# cblock-vrs.net
KiCad netlist of a schematic drawn in EAGLE
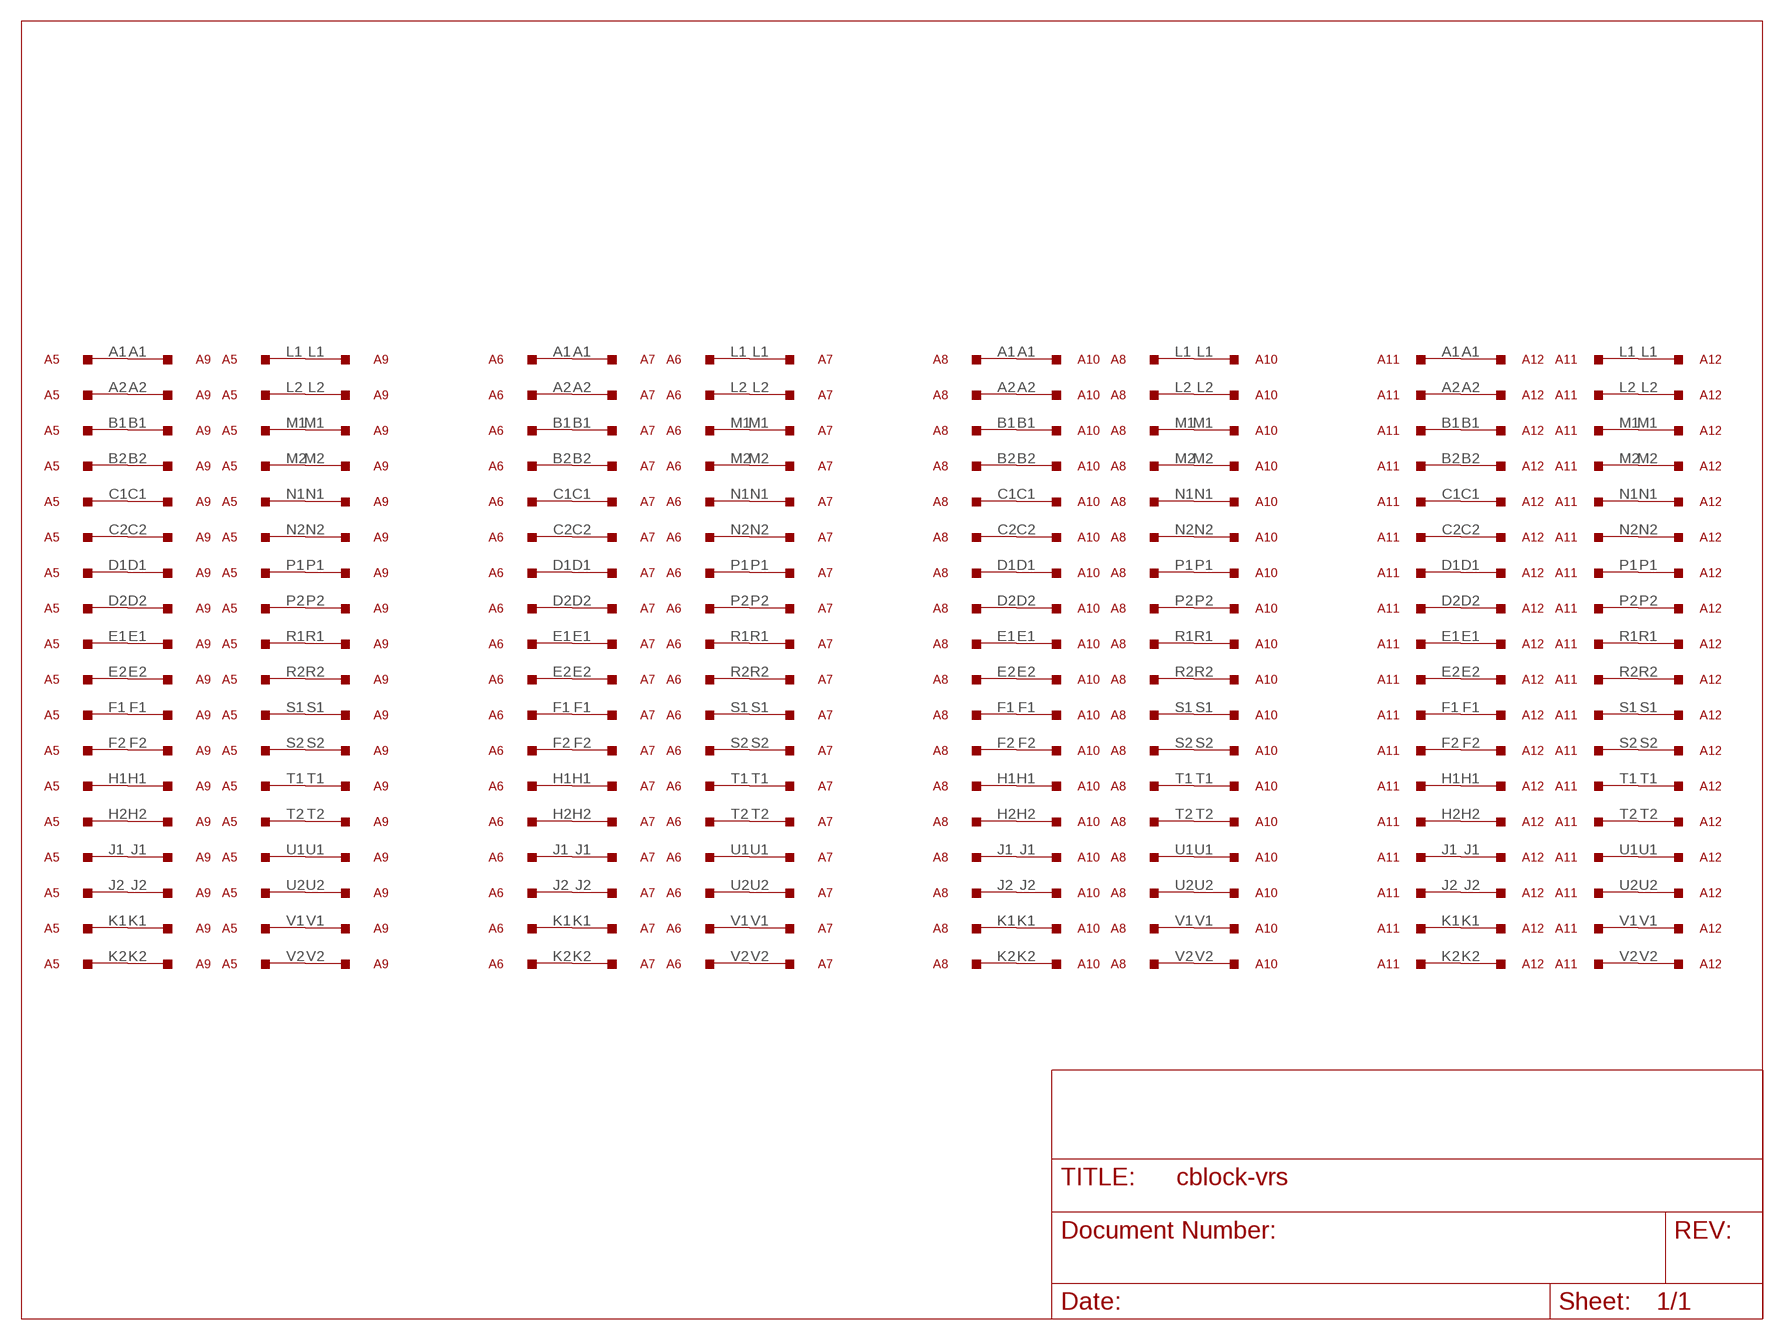
[diagram p0: schematic, sheet 1]

(export (version "E")
  (design (tool "Eeschema 10.0.6"))
  (components
    (comp (ref "A5")
      (value "M916")
      (footprint "eagle-import:H807")
      (libsource (lib "eagle-import") (part "M916"))
    )
    (comp (ref "A6")
      (value "M916")
      (footprint "eagle-import:H807")
      (libsource (lib "eagle-import") (part "M916"))
    )
    (comp (ref "A7")
      (value "M916")
      (footprint "eagle-import:H807")
      (libsource (lib "eagle-import") (part "M916"))
    )
    (comp (ref "A8")
      (value "M916")
      (footprint "eagle-import:H807")
      (libsource (lib "eagle-import") (part "M916"))
    )
    (comp (ref "A9")
      (value "M916")
      (footprint "eagle-import:H807")
      (libsource (lib "eagle-import") (part "M916"))
    )
    (comp (ref "A10")
      (value "M916")
      (footprint "eagle-import:H807")
      (libsource (lib "eagle-import") (part "M916"))
    )
    (comp (ref "A11")
      (value "M916")
      (footprint "eagle-import:H807")
      (libsource (lib "eagle-import") (part "M916"))
    )
    (comp (ref "A12")
      (value "M916")
      (footprint "eagle-import:H807")
      (libsource (lib "eagle-import") (part "M916"))
    )
  )
  (nets
    (net (code "1") (name "Net-(A5A-P$2)") (class "Default")
      (node (ref "A5") (pin "A1") (pinfunction "P$2_A1") (pintype "bidirectional"))
      (node (ref "A9") (pin "A1") (pinfunction "P$2_A1") (pintype "bidirectional"))
    )
    (net (code "2") (name "Net-(A5AA-P$2)") (class "Default")
      (node (ref "A5") (pin "R1") (pinfunction "P$2_R1") (pintype "bidirectional"))
      (node (ref "A9") (pin "R1") (pinfunction "P$2_R1") (pintype "bidirectional"))
    )
    (net (code "3") (name "Net-(A5AB-P$2)") (class "Default")
      (node (ref "A5") (pin "R2") (pinfunction "P$2_R2") (pintype "bidirectional"))
      (node (ref "A9") (pin "R2") (pinfunction "P$2_R2") (pintype "bidirectional"))
    )
    (net (code "4") (name "Net-(A5AC-P$2)") (class "Default")
      (node (ref "A5") (pin "S1") (pinfunction "P$2_S1") (pintype "bidirectional"))
      (node (ref "A9") (pin "S1") (pinfunction "P$2_S1") (pintype "bidirectional"))
    )
    (net (code "5") (name "Net-(A5AD-P$2)") (class "Default")
      (node (ref "A5") (pin "S2") (pinfunction "P$2_S2") (pintype "bidirectional"))
      (node (ref "A9") (pin "S2") (pinfunction "P$2_S2") (pintype "bidirectional"))
    )
    (net (code "6") (name "Net-(A5AE-P$2)") (class "Default")
      (node (ref "A5") (pin "T1") (pinfunction "P$2_T1") (pintype "bidirectional"))
      (node (ref "A9") (pin "T1") (pinfunction "P$2_T1") (pintype "bidirectional"))
    )
    (net (code "7") (name "Net-(A5AF-P$2)") (class "Default")
      (node (ref "A5") (pin "T2") (pinfunction "P$2_T2") (pintype "bidirectional"))
      (node (ref "A9") (pin "T2") (pinfunction "P$2_T2") (pintype "bidirectional"))
    )
    (net (code "8") (name "Net-(A5AG-P$2)") (class "Default")
      (node (ref "A5") (pin "U1") (pinfunction "P$2_U1") (pintype "bidirectional"))
      (node (ref "A9") (pin "U1") (pinfunction "P$2_U1") (pintype "bidirectional"))
    )
    (net (code "9") (name "Net-(A5AH-P$2)") (class "Default")
      (node (ref "A5") (pin "U2") (pinfunction "P$2_U2") (pintype "bidirectional"))
      (node (ref "A9") (pin "U2") (pinfunction "P$2_U2") (pintype "bidirectional"))
    )
    (net (code "10") (name "Net-(A5AI-P$2)") (class "Default")
      (node (ref "A5") (pin "V1") (pinfunction "P$2_V1") (pintype "bidirectional"))
      (node (ref "A9") (pin "V1") (pinfunction "P$2_V1") (pintype "bidirectional"))
    )
    (net (code "11") (name "Net-(A5AJ-P$2)") (class "Default")
      (node (ref "A5") (pin "V2") (pinfunction "P$2_V2") (pintype "bidirectional"))
      (node (ref "A9") (pin "V2") (pinfunction "P$2_V2") (pintype "bidirectional"))
    )
    (net (code "12") (name "Net-(A5B-P$2)") (class "Default")
      (node (ref "A5") (pin "A2") (pinfunction "P$2_A2") (pintype "bidirectional"))
      (node (ref "A9") (pin "A2") (pinfunction "P$2_A2") (pintype "bidirectional"))
    )
    (net (code "13") (name "Net-(A5C-P$2)") (class "Default")
      (node (ref "A5") (pin "B1") (pinfunction "P$2_B1") (pintype "bidirectional"))
      (node (ref "A9") (pin "B1") (pinfunction "P$2_B1") (pintype "bidirectional"))
    )
    (net (code "14") (name "Net-(A5D-P$2)") (class "Default")
      (node (ref "A5") (pin "B2") (pinfunction "P$2_B2") (pintype "bidirectional"))
      (node (ref "A9") (pin "B2") (pinfunction "P$2_B2") (pintype "bidirectional"))
    )
    (net (code "15") (name "Net-(A5E-P$2)") (class "Default")
      (node (ref "A5") (pin "C1") (pinfunction "P$2_C1") (pintype "bidirectional"))
      (node (ref "A9") (pin "C1") (pinfunction "P$2_C1") (pintype "bidirectional"))
    )
    (net (code "16") (name "Net-(A5F-P$2)") (class "Default")
      (node (ref "A5") (pin "C2") (pinfunction "P$2_C2") (pintype "bidirectional"))
      (node (ref "A9") (pin "C2") (pinfunction "P$2_C2") (pintype "bidirectional"))
    )
    (net (code "17") (name "Net-(A5G-P$2)") (class "Default")
      (node (ref "A5") (pin "D1") (pinfunction "P$2_D1") (pintype "bidirectional"))
      (node (ref "A9") (pin "D1") (pinfunction "P$2_D1") (pintype "bidirectional"))
    )
    (net (code "18") (name "Net-(A5H-P$2)") (class "Default")
      (node (ref "A5") (pin "D2") (pinfunction "P$2_D2") (pintype "bidirectional"))
      (node (ref "A9") (pin "D2") (pinfunction "P$2_D2") (pintype "bidirectional"))
    )
    (net (code "19") (name "Net-(A5I-P$2)") (class "Default")
      (node (ref "A5") (pin "E1") (pinfunction "P$2_E1") (pintype "bidirectional"))
      (node (ref "A9") (pin "E1") (pinfunction "P$2_E1") (pintype "bidirectional"))
    )
    (net (code "20") (name "Net-(A5J-P$2)") (class "Default")
      (node (ref "A5") (pin "E2") (pinfunction "P$2_E2") (pintype "bidirectional"))
      (node (ref "A9") (pin "E2") (pinfunction "P$2_E2") (pintype "bidirectional"))
    )
    (net (code "21") (name "Net-(A5K-P$2)") (class "Default")
      (node (ref "A5") (pin "F1") (pinfunction "P$2_F1") (pintype "bidirectional"))
      (node (ref "A9") (pin "F1") (pinfunction "P$2_F1") (pintype "bidirectional"))
    )
    (net (code "22") (name "Net-(A5L-P$2)") (class "Default")
      (node (ref "A5") (pin "F2") (pinfunction "P$2_F2") (pintype "bidirectional"))
      (node (ref "A9") (pin "F2") (pinfunction "P$2_F2") (pintype "bidirectional"))
    )
    (net (code "23") (name "Net-(A5M-P$2)") (class "Default")
      (node (ref "A5") (pin "H1") (pinfunction "P$2_H1") (pintype "bidirectional"))
      (node (ref "A9") (pin "H1") (pinfunction "P$2_H1") (pintype "bidirectional"))
    )
    (net (code "24") (name "Net-(A5N-P$2)") (class "Default")
      (node (ref "A5") (pin "H2") (pinfunction "P$2_H2") (pintype "bidirectional"))
      (node (ref "A9") (pin "H2") (pinfunction "P$2_H2") (pintype "bidirectional"))
    )
    (net (code "25") (name "Net-(A5O-P$2)") (class "Default")
      (node (ref "A5") (pin "J1") (pinfunction "P$2_J1") (pintype "bidirectional"))
      (node (ref "A9") (pin "J1") (pinfunction "P$2_J1") (pintype "bidirectional"))
    )
    (net (code "26") (name "Net-(A5P-P$2)") (class "Default")
      (node (ref "A5") (pin "J2") (pinfunction "P$2_J2") (pintype "bidirectional"))
      (node (ref "A9") (pin "J2") (pinfunction "P$2_J2") (pintype "bidirectional"))
    )
    (net (code "27") (name "Net-(A5Q-P$2)") (class "Default")
      (node (ref "A5") (pin "K1") (pinfunction "P$2_K1") (pintype "bidirectional"))
      (node (ref "A9") (pin "K1") (pinfunction "P$2_K1") (pintype "bidirectional"))
    )
    (net (code "28") (name "Net-(A5R-P$2)") (class "Default")
      (node (ref "A5") (pin "K2") (pinfunction "P$2_K2") (pintype "bidirectional"))
      (node (ref "A9") (pin "K2") (pinfunction "P$2_K2") (pintype "bidirectional"))
    )
    (net (code "29") (name "Net-(A5S-P$2)") (class "Default")
      (node (ref "A5") (pin "L1") (pinfunction "P$2_L1") (pintype "bidirectional"))
      (node (ref "A9") (pin "L1") (pinfunction "P$2_L1") (pintype "bidirectional"))
    )
    (net (code "30") (name "Net-(A5T-P$2)") (class "Default")
      (node (ref "A5") (pin "L2") (pinfunction "P$2_L2") (pintype "bidirectional"))
      (node (ref "A9") (pin "L2") (pinfunction "P$2_L2") (pintype "bidirectional"))
    )
    (net (code "31") (name "Net-(A5U-P$2)") (class "Default")
      (node (ref "A5") (pin "M1") (pinfunction "P$2_M1") (pintype "bidirectional"))
      (node (ref "A9") (pin "M1") (pinfunction "P$2_M1") (pintype "bidirectional"))
    )
    (net (code "32") (name "Net-(A5V-P$2)") (class "Default")
      (node (ref "A5") (pin "M2") (pinfunction "P$2_M2") (pintype "bidirectional"))
      (node (ref "A9") (pin "M2") (pinfunction "P$2_M2") (pintype "bidirectional"))
    )
    (net (code "33") (name "Net-(A5W-P$2)") (class "Default")
      (node (ref "A5") (pin "N1") (pinfunction "P$2_N1") (pintype "bidirectional"))
      (node (ref "A9") (pin "N1") (pinfunction "P$2_N1") (pintype "bidirectional"))
    )
    (net (code "34") (name "Net-(A5X-P$2)") (class "Default")
      (node (ref "A5") (pin "N2") (pinfunction "P$2_N2") (pintype "bidirectional"))
      (node (ref "A9") (pin "N2") (pinfunction "P$2_N2") (pintype "bidirectional"))
    )
    (net (code "35") (name "Net-(A5Y-P$2)") (class "Default")
      (node (ref "A5") (pin "P1") (pinfunction "P$2_P1") (pintype "bidirectional"))
      (node (ref "A9") (pin "P1") (pinfunction "P$2_P1") (pintype "bidirectional"))
    )
    (net (code "36") (name "Net-(A5Z-P$2)") (class "Default")
      (node (ref "A5") (pin "P2") (pinfunction "P$2_P2") (pintype "bidirectional"))
      (node (ref "A9") (pin "P2") (pinfunction "P$2_P2") (pintype "bidirectional"))
    )
    (net (code "37") (name "Net-(A6A-P$2)") (class "Default")
      (node (ref "A6") (pin "A1") (pinfunction "P$2_A1") (pintype "bidirectional"))
      (node (ref "A7") (pin "A1") (pinfunction "P$2_A1") (pintype "bidirectional"))
    )
    (net (code "38") (name "Net-(A6AA-P$2)") (class "Default")
      (node (ref "A6") (pin "R1") (pinfunction "P$2_R1") (pintype "bidirectional"))
      (node (ref "A7") (pin "R1") (pinfunction "P$2_R1") (pintype "bidirectional"))
    )
    (net (code "39") (name "Net-(A6AB-P$2)") (class "Default")
      (node (ref "A6") (pin "R2") (pinfunction "P$2_R2") (pintype "bidirectional"))
      (node (ref "A7") (pin "R2") (pinfunction "P$2_R2") (pintype "bidirectional"))
    )
    (net (code "40") (name "Net-(A6AC-P$2)") (class "Default")
      (node (ref "A6") (pin "S1") (pinfunction "P$2_S1") (pintype "bidirectional"))
      (node (ref "A7") (pin "S1") (pinfunction "P$2_S1") (pintype "bidirectional"))
    )
    (net (code "41") (name "Net-(A6AD-P$2)") (class "Default")
      (node (ref "A6") (pin "S2") (pinfunction "P$2_S2") (pintype "bidirectional"))
      (node (ref "A7") (pin "S2") (pinfunction "P$2_S2") (pintype "bidirectional"))
    )
    (net (code "42") (name "Net-(A6AE-P$2)") (class "Default")
      (node (ref "A6") (pin "T1") (pinfunction "P$2_T1") (pintype "bidirectional"))
      (node (ref "A7") (pin "T1") (pinfunction "P$2_T1") (pintype "bidirectional"))
    )
    (net (code "43") (name "Net-(A6AF-P$2)") (class "Default")
      (node (ref "A6") (pin "T2") (pinfunction "P$2_T2") (pintype "bidirectional"))
      (node (ref "A7") (pin "T2") (pinfunction "P$2_T2") (pintype "bidirectional"))
    )
    (net (code "44") (name "Net-(A6AG-P$2)") (class "Default")
      (node (ref "A6") (pin "U1") (pinfunction "P$2_U1") (pintype "bidirectional"))
      (node (ref "A7") (pin "U1") (pinfunction "P$2_U1") (pintype "bidirectional"))
    )
    (net (code "45") (name "Net-(A6AH-P$2)") (class "Default")
      (node (ref "A6") (pin "U2") (pinfunction "P$2_U2") (pintype "bidirectional"))
      (node (ref "A7") (pin "U2") (pinfunction "P$2_U2") (pintype "bidirectional"))
    )
    (net (code "46") (name "Net-(A6AI-P$2)") (class "Default")
      (node (ref "A6") (pin "V1") (pinfunction "P$2_V1") (pintype "bidirectional"))
      (node (ref "A7") (pin "V1") (pinfunction "P$2_V1") (pintype "bidirectional"))
    )
    (net (code "47") (name "Net-(A6AJ-P$2)") (class "Default")
      (node (ref "A6") (pin "V2") (pinfunction "P$2_V2") (pintype "bidirectional"))
      (node (ref "A7") (pin "V2") (pinfunction "P$2_V2") (pintype "bidirectional"))
    )
    (net (code "48") (name "Net-(A6B-P$2)") (class "Default")
      (node (ref "A6") (pin "A2") (pinfunction "P$2_A2") (pintype "bidirectional"))
      (node (ref "A7") (pin "A2") (pinfunction "P$2_A2") (pintype "bidirectional"))
    )
    (net (code "49") (name "Net-(A6C-P$2)") (class "Default")
      (node (ref "A6") (pin "B1") (pinfunction "P$2_B1") (pintype "bidirectional"))
      (node (ref "A7") (pin "B1") (pinfunction "P$2_B1") (pintype "bidirectional"))
    )
    (net (code "50") (name "Net-(A6D-P$2)") (class "Default")
      (node (ref "A6") (pin "B2") (pinfunction "P$2_B2") (pintype "bidirectional"))
      (node (ref "A7") (pin "B2") (pinfunction "P$2_B2") (pintype "bidirectional"))
    )
    (net (code "51") (name "Net-(A6E-P$2)") (class "Default")
      (node (ref "A6") (pin "C1") (pinfunction "P$2_C1") (pintype "bidirectional"))
      (node (ref "A7") (pin "C1") (pinfunction "P$2_C1") (pintype "bidirectional"))
    )
    (net (code "52") (name "Net-(A6F-P$2)") (class "Default")
      (node (ref "A6") (pin "C2") (pinfunction "P$2_C2") (pintype "bidirectional"))
      (node (ref "A7") (pin "C2") (pinfunction "P$2_C2") (pintype "bidirectional"))
    )
    (net (code "53") (name "Net-(A6G-P$2)") (class "Default")
      (node (ref "A6") (pin "D1") (pinfunction "P$2_D1") (pintype "bidirectional"))
      (node (ref "A7") (pin "D1") (pinfunction "P$2_D1") (pintype "bidirectional"))
    )
    (net (code "54") (name "Net-(A6H-P$2)") (class "Default")
      (node (ref "A6") (pin "D2") (pinfunction "P$2_D2") (pintype "bidirectional"))
      (node (ref "A7") (pin "D2") (pinfunction "P$2_D2") (pintype "bidirectional"))
    )
    (net (code "55") (name "Net-(A6I-P$2)") (class "Default")
      (node (ref "A6") (pin "E1") (pinfunction "P$2_E1") (pintype "bidirectional"))
      (node (ref "A7") (pin "E1") (pinfunction "P$2_E1") (pintype "bidirectional"))
    )
    (net (code "56") (name "Net-(A6J-P$2)") (class "Default")
      (node (ref "A6") (pin "E2") (pinfunction "P$2_E2") (pintype "bidirectional"))
      (node (ref "A7") (pin "E2") (pinfunction "P$2_E2") (pintype "bidirectional"))
    )
    (net (code "57") (name "Net-(A6K-P$2)") (class "Default")
      (node (ref "A6") (pin "F1") (pinfunction "P$2_F1") (pintype "bidirectional"))
      (node (ref "A7") (pin "F1") (pinfunction "P$2_F1") (pintype "bidirectional"))
    )
    (net (code "58") (name "Net-(A6L-P$2)") (class "Default")
      (node (ref "A6") (pin "F2") (pinfunction "P$2_F2") (pintype "bidirectional"))
      (node (ref "A7") (pin "F2") (pinfunction "P$2_F2") (pintype "bidirectional"))
    )
    (net (code "59") (name "Net-(A6M-P$2)") (class "Default")
      (node (ref "A6") (pin "H1") (pinfunction "P$2_H1") (pintype "bidirectional"))
      (node (ref "A7") (pin "H1") (pinfunction "P$2_H1") (pintype "bidirectional"))
    )
    (net (code "60") (name "Net-(A6N-P$2)") (class "Default")
      (node (ref "A6") (pin "H2") (pinfunction "P$2_H2") (pintype "bidirectional"))
      (node (ref "A7") (pin "H2") (pinfunction "P$2_H2") (pintype "bidirectional"))
    )
    (net (code "61") (name "Net-(A6O-P$2)") (class "Default")
      (node (ref "A6") (pin "J1") (pinfunction "P$2_J1") (pintype "bidirectional"))
      (node (ref "A7") (pin "J1") (pinfunction "P$2_J1") (pintype "bidirectional"))
    )
    (net (code "62") (name "Net-(A6P-P$2)") (class "Default")
      (node (ref "A6") (pin "J2") (pinfunction "P$2_J2") (pintype "bidirectional"))
      (node (ref "A7") (pin "J2") (pinfunction "P$2_J2") (pintype "bidirectional"))
    )
    (net (code "63") (name "Net-(A6Q-P$2)") (class "Default")
      (node (ref "A6") (pin "K1") (pinfunction "P$2_K1") (pintype "bidirectional"))
      (node (ref "A7") (pin "K1") (pinfunction "P$2_K1") (pintype "bidirectional"))
    )
    (net (code "64") (name "Net-(A6R-P$2)") (class "Default")
      (node (ref "A6") (pin "K2") (pinfunction "P$2_K2") (pintype "bidirectional"))
      (node (ref "A7") (pin "K2") (pinfunction "P$2_K2") (pintype "bidirectional"))
    )
    (net (code "65") (name "Net-(A6S-P$2)") (class "Default")
      (node (ref "A6") (pin "L1") (pinfunction "P$2_L1") (pintype "bidirectional"))
      (node (ref "A7") (pin "L1") (pinfunction "P$2_L1") (pintype "bidirectional"))
    )
    (net (code "66") (name "Net-(A6T-P$2)") (class "Default")
      (node (ref "A6") (pin "L2") (pinfunction "P$2_L2") (pintype "bidirectional"))
      (node (ref "A7") (pin "L2") (pinfunction "P$2_L2") (pintype "bidirectional"))
    )
    (net (code "67") (name "Net-(A6U-P$2)") (class "Default")
      (node (ref "A6") (pin "M1") (pinfunction "P$2_M1") (pintype "bidirectional"))
      (node (ref "A7") (pin "M1") (pinfunction "P$2_M1") (pintype "bidirectional"))
    )
    (net (code "68") (name "Net-(A6V-P$2)") (class "Default")
      (node (ref "A6") (pin "M2") (pinfunction "P$2_M2") (pintype "bidirectional"))
      (node (ref "A7") (pin "M2") (pinfunction "P$2_M2") (pintype "bidirectional"))
    )
    (net (code "69") (name "Net-(A6W-P$2)") (class "Default")
      (node (ref "A6") (pin "N1") (pinfunction "P$2_N1") (pintype "bidirectional"))
      (node (ref "A7") (pin "N1") (pinfunction "P$2_N1") (pintype "bidirectional"))
    )
    (net (code "70") (name "Net-(A6X-P$2)") (class "Default")
      (node (ref "A6") (pin "N2") (pinfunction "P$2_N2") (pintype "bidirectional"))
      (node (ref "A7") (pin "N2") (pinfunction "P$2_N2") (pintype "bidirectional"))
    )
    (net (code "71") (name "Net-(A6Y-P$2)") (class "Default")
      (node (ref "A6") (pin "P1") (pinfunction "P$2_P1") (pintype "bidirectional"))
      (node (ref "A7") (pin "P1") (pinfunction "P$2_P1") (pintype "bidirectional"))
    )
    (net (code "72") (name "Net-(A6Z-P$2)") (class "Default")
      (node (ref "A6") (pin "P2") (pinfunction "P$2_P2") (pintype "bidirectional"))
      (node (ref "A7") (pin "P2") (pinfunction "P$2_P2") (pintype "bidirectional"))
    )
    (net (code "73") (name "Net-(A10A-P$2)") (class "Default")
      (node (ref "A10") (pin "A1") (pinfunction "P$2_A1") (pintype "bidirectional"))
      (node (ref "A8") (pin "A1") (pinfunction "P$2_A1") (pintype "bidirectional"))
    )
    (net (code "74") (name "Net-(A10AA-P$2)") (class "Default")
      (node (ref "A10") (pin "R1") (pinfunction "P$2_R1") (pintype "bidirectional"))
      (node (ref "A8") (pin "R1") (pinfunction "P$2_R1") (pintype "bidirectional"))
    )
    (net (code "75") (name "Net-(A10AB-P$2)") (class "Default")
      (node (ref "A10") (pin "R2") (pinfunction "P$2_R2") (pintype "bidirectional"))
      (node (ref "A8") (pin "R2") (pinfunction "P$2_R2") (pintype "bidirectional"))
    )
    (net (code "76") (name "Net-(A10AC-P$2)") (class "Default")
      (node (ref "A10") (pin "S1") (pinfunction "P$2_S1") (pintype "bidirectional"))
      (node (ref "A8") (pin "S1") (pinfunction "P$2_S1") (pintype "bidirectional"))
    )
    (net (code "77") (name "Net-(A10AD-P$2)") (class "Default")
      (node (ref "A10") (pin "S2") (pinfunction "P$2_S2") (pintype "bidirectional"))
      (node (ref "A8") (pin "S2") (pinfunction "P$2_S2") (pintype "bidirectional"))
    )
    (net (code "78") (name "Net-(A10AE-P$2)") (class "Default")
      (node (ref "A10") (pin "T1") (pinfunction "P$2_T1") (pintype "bidirectional"))
      (node (ref "A8") (pin "T1") (pinfunction "P$2_T1") (pintype "bidirectional"))
    )
    (net (code "79") (name "Net-(A10AF-P$2)") (class "Default")
      (node (ref "A10") (pin "T2") (pinfunction "P$2_T2") (pintype "bidirectional"))
      (node (ref "A8") (pin "T2") (pinfunction "P$2_T2") (pintype "bidirectional"))
    )
    (net (code "80") (name "Net-(A10AG-P$2)") (class "Default")
      (node (ref "A10") (pin "U1") (pinfunction "P$2_U1") (pintype "bidirectional"))
      (node (ref "A8") (pin "U1") (pinfunction "P$2_U1") (pintype "bidirectional"))
    )
    (net (code "81") (name "Net-(A10AH-P$2)") (class "Default")
      (node (ref "A10") (pin "U2") (pinfunction "P$2_U2") (pintype "bidirectional"))
      (node (ref "A8") (pin "U2") (pinfunction "P$2_U2") (pintype "bidirectional"))
    )
    (net (code "82") (name "Net-(A10AI-P$2)") (class "Default")
      (node (ref "A10") (pin "V1") (pinfunction "P$2_V1") (pintype "bidirectional"))
      (node (ref "A8") (pin "V1") (pinfunction "P$2_V1") (pintype "bidirectional"))
    )
    (net (code "83") (name "Net-(A10AJ-P$2)") (class "Default")
      (node (ref "A10") (pin "V2") (pinfunction "P$2_V2") (pintype "bidirectional"))
      (node (ref "A8") (pin "V2") (pinfunction "P$2_V2") (pintype "bidirectional"))
    )
    (net (code "84") (name "Net-(A10B-P$2)") (class "Default")
      (node (ref "A10") (pin "A2") (pinfunction "P$2_A2") (pintype "bidirectional"))
      (node (ref "A8") (pin "A2") (pinfunction "P$2_A2") (pintype "bidirectional"))
    )
    (net (code "85") (name "Net-(A10C-P$2)") (class "Default")
      (node (ref "A10") (pin "B1") (pinfunction "P$2_B1") (pintype "bidirectional"))
      (node (ref "A8") (pin "B1") (pinfunction "P$2_B1") (pintype "bidirectional"))
    )
    (net (code "86") (name "Net-(A10D-P$2)") (class "Default")
      (node (ref "A10") (pin "B2") (pinfunction "P$2_B2") (pintype "bidirectional"))
      (node (ref "A8") (pin "B2") (pinfunction "P$2_B2") (pintype "bidirectional"))
    )
    (net (code "87") (name "Net-(A10E-P$2)") (class "Default")
      (node (ref "A10") (pin "C1") (pinfunction "P$2_C1") (pintype "bidirectional"))
      (node (ref "A8") (pin "C1") (pinfunction "P$2_C1") (pintype "bidirectional"))
    )
    (net (code "88") (name "Net-(A10F-P$2)") (class "Default")
      (node (ref "A10") (pin "C2") (pinfunction "P$2_C2") (pintype "bidirectional"))
      (node (ref "A8") (pin "C2") (pinfunction "P$2_C2") (pintype "bidirectional"))
    )
    (net (code "89") (name "Net-(A10G-P$2)") (class "Default")
      (node (ref "A10") (pin "D1") (pinfunction "P$2_D1") (pintype "bidirectional"))
      (node (ref "A8") (pin "D1") (pinfunction "P$2_D1") (pintype "bidirectional"))
    )
    (net (code "90") (name "Net-(A10H-P$2)") (class "Default")
      (node (ref "A10") (pin "D2") (pinfunction "P$2_D2") (pintype "bidirectional"))
      (node (ref "A8") (pin "D2") (pinfunction "P$2_D2") (pintype "bidirectional"))
    )
    (net (code "91") (name "Net-(A10I-P$2)") (class "Default")
      (node (ref "A10") (pin "E1") (pinfunction "P$2_E1") (pintype "bidirectional"))
      (node (ref "A8") (pin "E1") (pinfunction "P$2_E1") (pintype "bidirectional"))
    )
    (net (code "92") (name "Net-(A10J-P$2)") (class "Default")
      (node (ref "A10") (pin "E2") (pinfunction "P$2_E2") (pintype "bidirectional"))
      (node (ref "A8") (pin "E2") (pinfunction "P$2_E2") (pintype "bidirectional"))
    )
    (net (code "93") (name "Net-(A10K-P$2)") (class "Default")
      (node (ref "A10") (pin "F1") (pinfunction "P$2_F1") (pintype "bidirectional"))
      (node (ref "A8") (pin "F1") (pinfunction "P$2_F1") (pintype "bidirectional"))
    )
    (net (code "94") (name "Net-(A10L-P$2)") (class "Default")
      (node (ref "A10") (pin "F2") (pinfunction "P$2_F2") (pintype "bidirectional"))
      (node (ref "A8") (pin "F2") (pinfunction "P$2_F2") (pintype "bidirectional"))
    )
    (net (code "95") (name "Net-(A10M-P$2)") (class "Default")
      (node (ref "A10") (pin "H1") (pinfunction "P$2_H1") (pintype "bidirectional"))
      (node (ref "A8") (pin "H1") (pinfunction "P$2_H1") (pintype "bidirectional"))
    )
    (net (code "96") (name "Net-(A10N-P$2)") (class "Default")
      (node (ref "A10") (pin "H2") (pinfunction "P$2_H2") (pintype "bidirectional"))
      (node (ref "A8") (pin "H2") (pinfunction "P$2_H2") (pintype "bidirectional"))
    )
    (net (code "97") (name "Net-(A10O-P$2)") (class "Default")
      (node (ref "A10") (pin "J1") (pinfunction "P$2_J1") (pintype "bidirectional"))
      (node (ref "A8") (pin "J1") (pinfunction "P$2_J1") (pintype "bidirectional"))
    )
    (net (code "98") (name "Net-(A10P-P$2)") (class "Default")
      (node (ref "A10") (pin "J2") (pinfunction "P$2_J2") (pintype "bidirectional"))
      (node (ref "A8") (pin "J2") (pinfunction "P$2_J2") (pintype "bidirectional"))
    )
    (net (code "99") (name "Net-(A10Q-P$2)") (class "Default")
      (node (ref "A10") (pin "K1") (pinfunction "P$2_K1") (pintype "bidirectional"))
      (node (ref "A8") (pin "K1") (pinfunction "P$2_K1") (pintype "bidirectional"))
    )
    (net (code "100") (name "Net-(A10R-P$2)") (class "Default")
      (node (ref "A10") (pin "K2") (pinfunction "P$2_K2") (pintype "bidirectional"))
      (node (ref "A8") (pin "K2") (pinfunction "P$2_K2") (pintype "bidirectional"))
    )
    (net (code "101") (name "Net-(A10S-P$2)") (class "Default")
      (node (ref "A10") (pin "L1") (pinfunction "P$2_L1") (pintype "bidirectional"))
      (node (ref "A8") (pin "L1") (pinfunction "P$2_L1") (pintype "bidirectional"))
    )
    (net (code "102") (name "Net-(A10T-P$2)") (class "Default")
      (node (ref "A10") (pin "L2") (pinfunction "P$2_L2") (pintype "bidirectional"))
      (node (ref "A8") (pin "L2") (pinfunction "P$2_L2") (pintype "bidirectional"))
    )
    (net (code "103") (name "Net-(A10U-P$2)") (class "Default")
      (node (ref "A10") (pin "M1") (pinfunction "P$2_M1") (pintype "bidirectional"))
      (node (ref "A8") (pin "M1") (pinfunction "P$2_M1") (pintype "bidirectional"))
    )
    (net (code "104") (name "Net-(A10V-P$2)") (class "Default")
      (node (ref "A10") (pin "M2") (pinfunction "P$2_M2") (pintype "bidirectional"))
      (node (ref "A8") (pin "M2") (pinfunction "P$2_M2") (pintype "bidirectional"))
    )
    (net (code "105") (name "Net-(A10W-P$2)") (class "Default")
      (node (ref "A10") (pin "N1") (pinfunction "P$2_N1") (pintype "bidirectional"))
      (node (ref "A8") (pin "N1") (pinfunction "P$2_N1") (pintype "bidirectional"))
    )
    (net (code "106") (name "Net-(A10X-P$2)") (class "Default")
      (node (ref "A10") (pin "N2") (pinfunction "P$2_N2") (pintype "bidirectional"))
      (node (ref "A8") (pin "N2") (pinfunction "P$2_N2") (pintype "bidirectional"))
    )
    (net (code "107") (name "Net-(A10Y-P$2)") (class "Default")
      (node (ref "A10") (pin "P1") (pinfunction "P$2_P1") (pintype "bidirectional"))
      (node (ref "A8") (pin "P1") (pinfunction "P$2_P1") (pintype "bidirectional"))
    )
    (net (code "108") (name "Net-(A10Z-P$2)") (class "Default")
      (node (ref "A10") (pin "P2") (pinfunction "P$2_P2") (pintype "bidirectional"))
      (node (ref "A8") (pin "P2") (pinfunction "P$2_P2") (pintype "bidirectional"))
    )
    (net (code "109") (name "Net-(A11A-P$2)") (class "Default")
      (node (ref "A11") (pin "A1") (pinfunction "P$2_A1") (pintype "bidirectional"))
      (node (ref "A12") (pin "A1") (pinfunction "P$2_A1") (pintype "bidirectional"))
    )
    (net (code "110") (name "Net-(A11AA-P$2)") (class "Default")
      (node (ref "A11") (pin "R1") (pinfunction "P$2_R1") (pintype "bidirectional"))
      (node (ref "A12") (pin "R1") (pinfunction "P$2_R1") (pintype "bidirectional"))
    )
    (net (code "111") (name "Net-(A11AB-P$2)") (class "Default")
      (node (ref "A11") (pin "R2") (pinfunction "P$2_R2") (pintype "bidirectional"))
      (node (ref "A12") (pin "R2") (pinfunction "P$2_R2") (pintype "bidirectional"))
    )
    (net (code "112") (name "Net-(A11AC-P$2)") (class "Default")
      (node (ref "A11") (pin "S1") (pinfunction "P$2_S1") (pintype "bidirectional"))
      (node (ref "A12") (pin "S1") (pinfunction "P$2_S1") (pintype "bidirectional"))
    )
    (net (code "113") (name "Net-(A11AD-P$2)") (class "Default")
      (node (ref "A11") (pin "S2") (pinfunction "P$2_S2") (pintype "bidirectional"))
      (node (ref "A12") (pin "S2") (pinfunction "P$2_S2") (pintype "bidirectional"))
    )
    (net (code "114") (name "Net-(A11AE-P$2)") (class "Default")
      (node (ref "A11") (pin "T1") (pinfunction "P$2_T1") (pintype "bidirectional"))
      (node (ref "A12") (pin "T1") (pinfunction "P$2_T1") (pintype "bidirectional"))
    )
    (net (code "115") (name "Net-(A11AF-P$2)") (class "Default")
      (node (ref "A11") (pin "T2") (pinfunction "P$2_T2") (pintype "bidirectional"))
      (node (ref "A12") (pin "T2") (pinfunction "P$2_T2") (pintype "bidirectional"))
    )
    (net (code "116") (name "Net-(A11AG-P$2)") (class "Default")
      (node (ref "A11") (pin "U1") (pinfunction "P$2_U1") (pintype "bidirectional"))
      (node (ref "A12") (pin "U1") (pinfunction "P$2_U1") (pintype "bidirectional"))
    )
    (net (code "117") (name "Net-(A11AH-P$2)") (class "Default")
      (node (ref "A11") (pin "U2") (pinfunction "P$2_U2") (pintype "bidirectional"))
      (node (ref "A12") (pin "U2") (pinfunction "P$2_U2") (pintype "bidirectional"))
    )
    (net (code "118") (name "Net-(A11AI-P$2)") (class "Default")
      (node (ref "A11") (pin "V1") (pinfunction "P$2_V1") (pintype "bidirectional"))
      (node (ref "A12") (pin "V1") (pinfunction "P$2_V1") (pintype "bidirectional"))
    )
    (net (code "119") (name "Net-(A11AJ-P$2)") (class "Default")
      (node (ref "A11") (pin "V2") (pinfunction "P$2_V2") (pintype "bidirectional"))
      (node (ref "A12") (pin "V2") (pinfunction "P$2_V2") (pintype "bidirectional"))
    )
    (net (code "120") (name "Net-(A11B-P$2)") (class "Default")
      (node (ref "A11") (pin "A2") (pinfunction "P$2_A2") (pintype "bidirectional"))
      (node (ref "A12") (pin "A2") (pinfunction "P$2_A2") (pintype "bidirectional"))
    )
    (net (code "121") (name "Net-(A11C-P$2)") (class "Default")
      (node (ref "A11") (pin "B1") (pinfunction "P$2_B1") (pintype "bidirectional"))
      (node (ref "A12") (pin "B1") (pinfunction "P$2_B1") (pintype "bidirectional"))
    )
    (net (code "122") (name "Net-(A11D-P$2)") (class "Default")
      (node (ref "A11") (pin "B2") (pinfunction "P$2_B2") (pintype "bidirectional"))
      (node (ref "A12") (pin "B2") (pinfunction "P$2_B2") (pintype "bidirectional"))
    )
    (net (code "123") (name "Net-(A11E-P$2)") (class "Default")
      (node (ref "A11") (pin "C1") (pinfunction "P$2_C1") (pintype "bidirectional"))
      (node (ref "A12") (pin "C1") (pinfunction "P$2_C1") (pintype "bidirectional"))
    )
    (net (code "124") (name "Net-(A11F-P$2)") (class "Default")
      (node (ref "A11") (pin "C2") (pinfunction "P$2_C2") (pintype "bidirectional"))
      (node (ref "A12") (pin "C2") (pinfunction "P$2_C2") (pintype "bidirectional"))
    )
    (net (code "125") (name "Net-(A11G-P$2)") (class "Default")
      (node (ref "A11") (pin "D1") (pinfunction "P$2_D1") (pintype "bidirectional"))
      (node (ref "A12") (pin "D1") (pinfunction "P$2_D1") (pintype "bidirectional"))
    )
    (net (code "126") (name "Net-(A11H-P$2)") (class "Default")
      (node (ref "A11") (pin "D2") (pinfunction "P$2_D2") (pintype "bidirectional"))
      (node (ref "A12") (pin "D2") (pinfunction "P$2_D2") (pintype "bidirectional"))
    )
    (net (code "127") (name "Net-(A11I-P$2)") (class "Default")
      (node (ref "A11") (pin "E1") (pinfunction "P$2_E1") (pintype "bidirectional"))
      (node (ref "A12") (pin "E1") (pinfunction "P$2_E1") (pintype "bidirectional"))
    )
    (net (code "128") (name "Net-(A11J-P$2)") (class "Default")
      (node (ref "A11") (pin "E2") (pinfunction "P$2_E2") (pintype "bidirectional"))
      (node (ref "A12") (pin "E2") (pinfunction "P$2_E2") (pintype "bidirectional"))
    )
    (net (code "129") (name "Net-(A11K-P$2)") (class "Default")
      (node (ref "A11") (pin "F1") (pinfunction "P$2_F1") (pintype "bidirectional"))
      (node (ref "A12") (pin "F1") (pinfunction "P$2_F1") (pintype "bidirectional"))
    )
    (net (code "130") (name "Net-(A11L-P$2)") (class "Default")
      (node (ref "A11") (pin "F2") (pinfunction "P$2_F2") (pintype "bidirectional"))
      (node (ref "A12") (pin "F2") (pinfunction "P$2_F2") (pintype "bidirectional"))
    )
    (net (code "131") (name "Net-(A11M-P$2)") (class "Default")
      (node (ref "A11") (pin "H1") (pinfunction "P$2_H1") (pintype "bidirectional"))
      (node (ref "A12") (pin "H1") (pinfunction "P$2_H1") (pintype "bidirectional"))
    )
    (net (code "132") (name "Net-(A11N-P$2)") (class "Default")
      (node (ref "A11") (pin "H2") (pinfunction "P$2_H2") (pintype "bidirectional"))
      (node (ref "A12") (pin "H2") (pinfunction "P$2_H2") (pintype "bidirectional"))
    )
    (net (code "133") (name "Net-(A11O-P$2)") (class "Default")
      (node (ref "A11") (pin "J1") (pinfunction "P$2_J1") (pintype "bidirectional"))
      (node (ref "A12") (pin "J1") (pinfunction "P$2_J1") (pintype "bidirectional"))
    )
    (net (code "134") (name "Net-(A11P-P$2)") (class "Default")
      (node (ref "A11") (pin "J2") (pinfunction "P$2_J2") (pintype "bidirectional"))
      (node (ref "A12") (pin "J2") (pinfunction "P$2_J2") (pintype "bidirectional"))
    )
    (net (code "135") (name "Net-(A11Q-P$2)") (class "Default")
      (node (ref "A11") (pin "K1") (pinfunction "P$2_K1") (pintype "bidirectional"))
      (node (ref "A12") (pin "K1") (pinfunction "P$2_K1") (pintype "bidirectional"))
    )
    (net (code "136") (name "Net-(A11R-P$2)") (class "Default")
      (node (ref "A11") (pin "K2") (pinfunction "P$2_K2") (pintype "bidirectional"))
      (node (ref "A12") (pin "K2") (pinfunction "P$2_K2") (pintype "bidirectional"))
    )
    (net (code "137") (name "Net-(A11S-P$2)") (class "Default")
      (node (ref "A11") (pin "L1") (pinfunction "P$2_L1") (pintype "bidirectional"))
      (node (ref "A12") (pin "L1") (pinfunction "P$2_L1") (pintype "bidirectional"))
    )
    (net (code "138") (name "Net-(A11T-P$2)") (class "Default")
      (node (ref "A11") (pin "L2") (pinfunction "P$2_L2") (pintype "bidirectional"))
      (node (ref "A12") (pin "L2") (pinfunction "P$2_L2") (pintype "bidirectional"))
    )
    (net (code "139") (name "Net-(A11U-P$2)") (class "Default")
      (node (ref "A11") (pin "M1") (pinfunction "P$2_M1") (pintype "bidirectional"))
      (node (ref "A12") (pin "M1") (pinfunction "P$2_M1") (pintype "bidirectional"))
    )
    (net (code "140") (name "Net-(A11V-P$2)") (class "Default")
      (node (ref "A11") (pin "M2") (pinfunction "P$2_M2") (pintype "bidirectional"))
      (node (ref "A12") (pin "M2") (pinfunction "P$2_M2") (pintype "bidirectional"))
    )
    (net (code "141") (name "Net-(A11W-P$2)") (class "Default")
      (node (ref "A11") (pin "N1") (pinfunction "P$2_N1") (pintype "bidirectional"))
      (node (ref "A12") (pin "N1") (pinfunction "P$2_N1") (pintype "bidirectional"))
    )
    (net (code "142") (name "Net-(A11X-P$2)") (class "Default")
      (node (ref "A11") (pin "N2") (pinfunction "P$2_N2") (pintype "bidirectional"))
      (node (ref "A12") (pin "N2") (pinfunction "P$2_N2") (pintype "bidirectional"))
    )
    (net (code "143") (name "Net-(A11Y-P$2)") (class "Default")
      (node (ref "A11") (pin "P1") (pinfunction "P$2_P1") (pintype "bidirectional"))
      (node (ref "A12") (pin "P1") (pinfunction "P$2_P1") (pintype "bidirectional"))
    )
    (net (code "144") (name "Net-(A11Z-P$2)") (class "Default")
      (node (ref "A11") (pin "P2") (pinfunction "P$2_P2") (pintype "bidirectional"))
      (node (ref "A12") (pin "P2") (pinfunction "P$2_P2") (pintype "bidirectional"))
    )
  )
)
